# 1-wire.net
KiCad netlist of a schematic drawn in Altium Designer
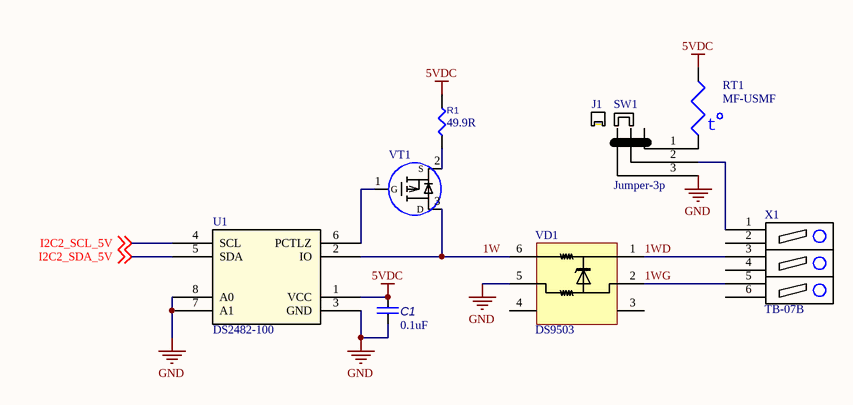
[diagram p0: 1-wire.SchDoc]

(export (version "E")
  (design (tool "Eeschema 10.0.6"))
  (components
    (comp (ref "C1")
      (value "0.1uF")
      (footprint "CC1608-0603")
      (description "C0603")
      (libsource (lib "spider") (part "C0603"))
    )
    (comp (ref "J1")
      (value "Jumper-cap")
      (description "Jumper")
      (libsource (lib "spider") (part "Jumper-cap"))
    )
    (comp (ref "R1")
      (value "49.9R")
      (footprint "RESC1608X55N")
      (description "R0603")
      (libsource (lib "spider") (part "R0603"))
    )
    (comp (ref "RT1")
      (value "MF-USMF")
      (footprint "MF-USMF")
      (description "PTC Resettable Fuses")
      (fields (field (name "MANUFACTURER") "Bourns"))
      (libsource (lib "spider") (part "MF-USMF"))
    )
    (comp (ref "SW1")
      (value "Jumper-3p")
      (footprint "pls-3")
      (description "PLS-3 2.54mm pin connector")
      (libsource (lib "spider") (part "Jumper-3p"))
    )
    (comp (ref "U1")
      (value "DS2482-100")
      (footprint "SOIC127P600X175-8N")
      (description "I2C - 1-Wire master single channel")
      (libsource (lib "spider") (part "DS2482-100"))
    )
    (comp (ref "VD1")
      (value "DS9503")
      (footprint "tsoc6")
      (description "ESD Protection Diode with Resistors")
      (libsource (lib "pmvent") (part "DS9503"))
    )
    (comp (ref "VT1")
      (value "P-FET SOT-23")
      (footprint "SO-G3")
      (description "P-FET transistor in SOT-23-3 package")
      (libsource (lib "spider") (part "P-FET SOT-23"))
    )
    (comp (ref "X1")
      (value "TB-07B")
      (footprint "TB-07B")
      (description "Terminal Block 3 pos")
      (libsource (lib "spider") (part "TB-07B"))
    )
  )
  (nets
    (net (code "1") (name "/1W") (class "Default")
      (node (ref "U1") (pin "2") (pinfunction "IO_2") (pintype "passive"))
      (node (ref "VD1") (pin "6") (pinfunction "6_6") (pintype "passive"))
      (node (ref "VT1") (pin "3") (pinfunction "D_3") (pintype "passive"))
    )
    (net (code "2") (name "/1WD") (class "Default")
      (node (ref "VD1") (pin "1") (pinfunction "1_1") (pintype "passive"))
      (node (ref "X1") (pin "3") (pinfunction "3_3") (pintype "passive"))
    )
    (net (code "3") (name "/1WG") (class "Default")
      (node (ref "VD1") (pin "2") (pinfunction "2_2") (pintype "passive"))
      (node (ref "X1") (pin "5") (pinfunction "5_5") (pintype "passive"))
    )
    (net (code "4") (name "5VDC") (class "Default")
      (node (ref "C1") (pin "1") (pinfunction "1_1") (pintype "passive"))
      (node (ref "R1") (pin "2") (pinfunction "2_2") (pintype "passive"))
      (node (ref "RT1") (pin "1") (pinfunction "1_1") (pintype "passive"))
      (node (ref "U1") (pin "1") (pinfunction "VCC_1") (pintype "passive"))
    )
    (net (code "5") (name "GND") (class "Default")
      (node (ref "C1") (pin "2") (pinfunction "2_2") (pintype "passive"))
      (node (ref "SW1") (pin "3") (pinfunction "3_3") (pintype "passive"))
      (node (ref "U1") (pin "3") (pinfunction "GND_3") (pintype "passive"))
      (node (ref "U1") (pin "7") (pinfunction "A1_7") (pintype "passive"))
      (node (ref "U1") (pin "8") (pinfunction "A0_8") (pintype "passive"))
      (node (ref "VD1") (pin "5") (pinfunction "5_5") (pintype "passive"))
    )
    (net (code "6") (name "I2C2_SCL_5V") (class "Default")
      (node (ref "U1") (pin "4") (pinfunction "SCL_4") (pintype "passive"))
    )
    (net (code "7") (name "I2C2_SDA_5V") (class "Default")
      (node (ref "U1") (pin "5") (pinfunction "SDA_5") (pintype "passive"))
    )
    (net (code "8") (name "Net-(RT1-Pad2)") (class "Default")
      (node (ref "RT1") (pin "2") (pinfunction "2_2") (pintype "passive"))
      (node (ref "SW1") (pin "1") (pinfunction "1_1") (pintype "passive"))
    )
    (net (code "9") (name "Net-(SW1-Pad2)") (class "Default")
      (node (ref "SW1") (pin "2") (pinfunction "2_2") (pintype "passive"))
      (node (ref "X1") (pin "1") (pinfunction "1_1") (pintype "passive"))
    )
    (net (code "10") (name "Net-(U1-PCTLZ)") (class "Default")
      (node (ref "U1") (pin "6") (pinfunction "PCTLZ_6") (pintype "passive"))
      (node (ref "VT1") (pin "1") (pinfunction "G_1") (pintype "passive"))
    )
    (net (code "11") (name "Net-(VT1-S)") (class "Default")
      (node (ref "R1") (pin "1") (pinfunction "1_1") (pintype "passive"))
      (node (ref "VT1") (pin "2") (pinfunction "S_2") (pintype "passive"))
    )
    (net (code "12") (name "unconnected-(VD1-Pad3)") (class "Default")
      (node (ref "VD1") (pin "3") (pinfunction "3_3") (pintype "passive"))
    )
    (net (code "13") (name "unconnected-(VD1-Pad4)") (class "Default")
      (node (ref "VD1") (pin "4") (pinfunction "4_4") (pintype "passive"))
    )
    (net (code "14") (name "unconnected-(X1-Pad2)") (class "Default")
      (node (ref "X1") (pin "2") (pinfunction "2_2") (pintype "passive"))
    )
    (net (code "15") (name "unconnected-(X1-Pad4)") (class "Default")
      (node (ref "X1") (pin "4") (pinfunction "4_4") (pintype "passive"))
    )
    (net (code "16") (name "unconnected-(X1-Pad6)") (class "Default")
      (node (ref "X1") (pin "6") (pinfunction "6_6") (pintype "passive"))
    )
  )
)
